# wireless_charger_controller.net
KiCad netlist of a schematic drawn in EasyEDA Pro
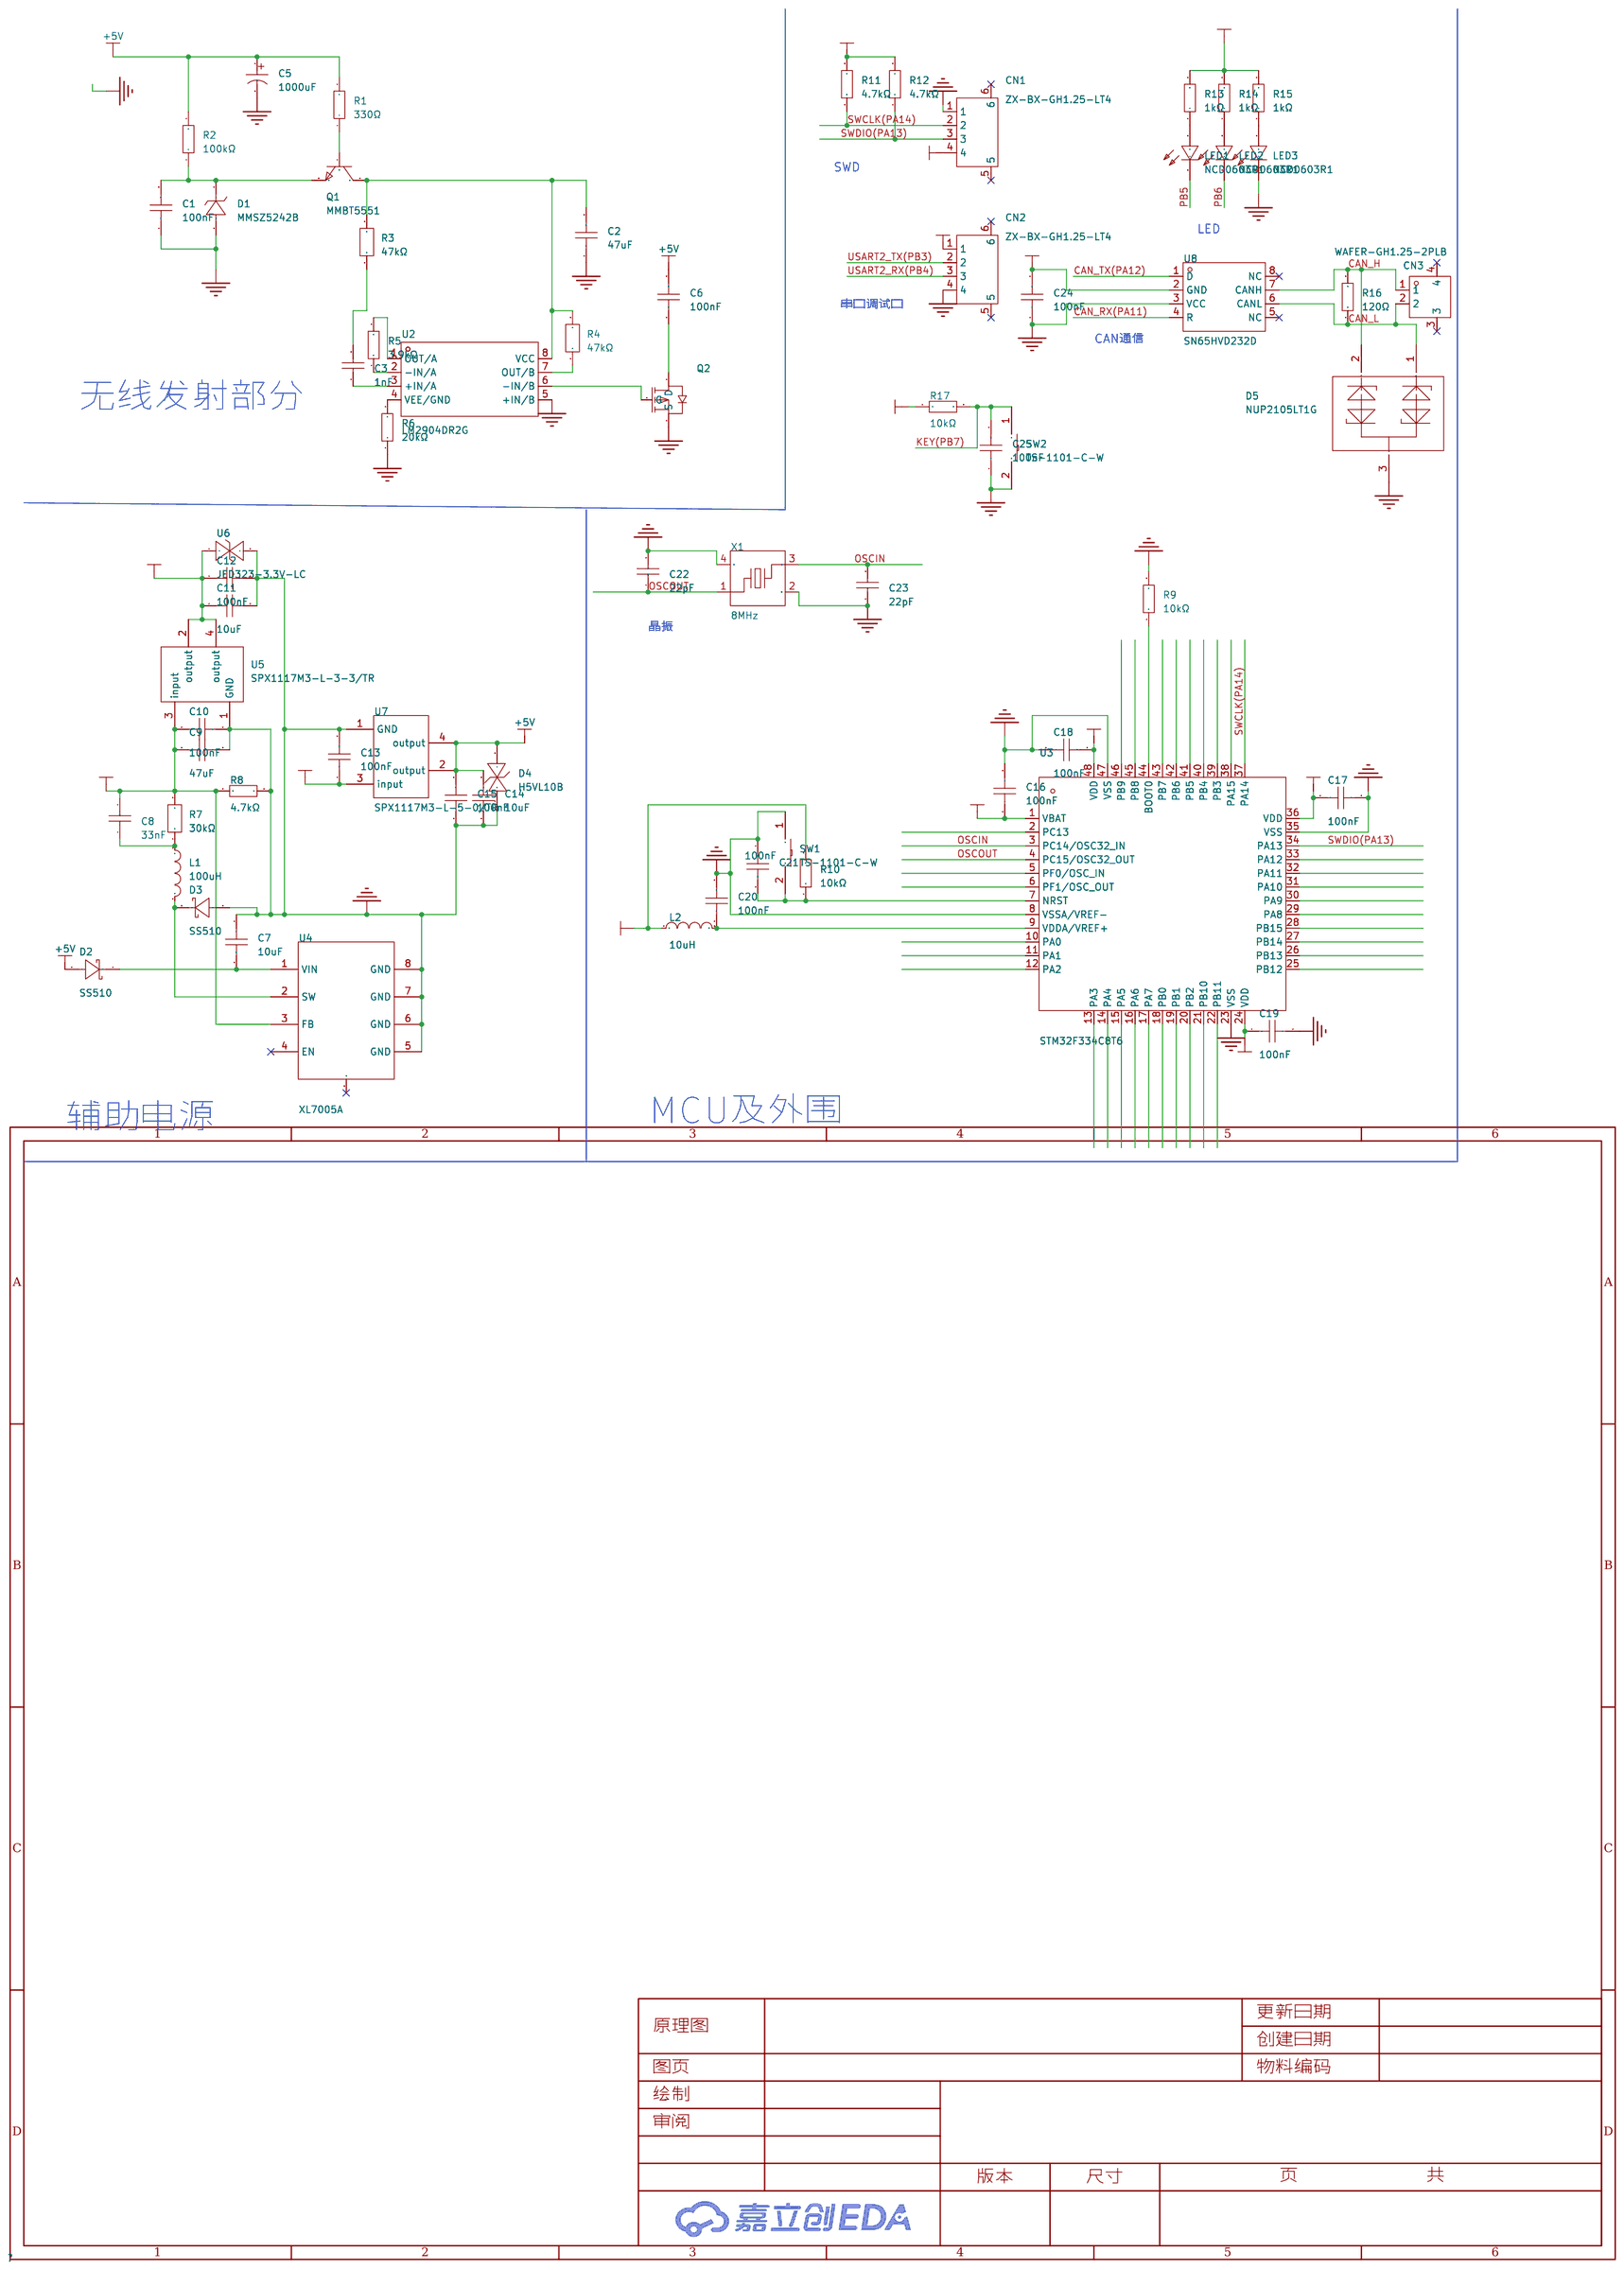
[diagram p0: schematic sheet]

(export (version "E")
  (design (tool "Eeschema 10.0.6"))
  (components
    (comp (ref "C1")
      (value "100nF")
      (footprint "easyedapro:C0603")
      (description "容值:100nF;精度:±10%;额定电压:50V;材质(温度系数):X7R;")
      (fields
        (field (name "Manufacturer Part") "CGA0603X7R104K500JT")
        (field (name "Manufacturer") "HRE(芯声)")
      )
      (libsource (lib "easyedapro") (part "CGA0603X7R104K500JT"))
    )
    (comp (ref "C2")
      (value "47uF")
      (footprint "easyedapro:C1206")
      (description "容值:47uF;精度:±20%;额定电压:16V;材质(温度系数):X5R;")
      (fields
        (field (name "Manufacturer Part") "HGC1206R5476M160NSPJ")
        (field (name "Manufacturer") "Chinocera(华瓷)")
      )
      (libsource (lib "easyedapro") (part "HGC1206R5476M160NSPJ"))
    )
    (comp (ref "C3")
      (value "1nF")
      (footprint "easyedapro:C0603")
      (description "容值:1nF;精度:±5%;额定电压:50V;材质(温度系数):NP0;")
      (fields
        (field (name "Manufacturer Part") "CC0603JRNPO9BN102")
        (field (name "Manufacturer") "YAGEO(国巨)")
      )
      (libsource (lib "easyedapro") (part "CC0603JRNPO9BN102"))
    )
    (comp (ref "C5")
      (value "1000uF")
      (footprint "easyedapro:CAP-TH_BD13.0-P5.00-D1.2-FD")
      (description "容值:1000uF;精度:±20%;额定电压:35V;")
      (fields
        (field (name "Manufacturer Part") "35YXJ1000M12.5X20")
        (field (name "Manufacturer") "rubycon(红宝石)")
      )
      (libsource (lib "easyedapro") (part "35YXJ1000M12.5X20"))
    )
    (comp (ref "C6")
      (value "100nF")
      (footprint "easyedapro:C1206")
      (description "容值:100nF;精度:±10%;额定电压:250V;材质(温度系数):X7R;")
      (fields
        (field (name "Manufacturer Part") "CGA1206X7R104K251NT")
        (field (name "Manufacturer") "HRE(芯声)")
      )
      (libsource (lib "easyedapro") (part "CGA1206X7R104K251NT"))
    )
    (comp (ref "C7")
      (value "10uF")
      (footprint "easyedapro:C1206")
      (description "容值:10uF;精度:±10%;额定电压:50V;材质(温度系数):X5R;")
      (fields
        (field (name "Manufacturer Part") "HGC1206R5106K500NSPJ")
        (field (name "Manufacturer") "Chinocera(华瓷)")
      )
      (libsource (lib "easyedapro") (part "HGC1206R5106K500NSPJ"))
    )
    (comp (ref "C8")
      (value "33nF")
      (footprint "easyedapro:C0603")
      (description "容值:33nF;精度:±10%;额定电压:50V;材质(温度系数):X7R;")
      (fields
        (field (name "Manufacturer Part") "CL10B333KB8NNNC")
        (field (name "Manufacturer") "SAMSUNG(三星)")
      )
      (libsource (lib "easyedapro") (part "CL10B333KB8NNNC"))
    )
    (comp (ref "C9")
      (value "47uF")
      (footprint "easyedapro:C1206")
      (description "容值:47uF;精度:±20%;额定电压:25V;材质(温度系数):X5R;")
      (fields
        (field (name "Manufacturer Part") "HGC1206R5476M250NSPJ")
        (field (name "Manufacturer") "Chinocera(华瓷)")
      )
      (libsource (lib "easyedapro") (part "HGC1206R5476M250NSPJ"))
    )
    (comp (ref "C10")
      (value "100nF")
      (footprint "easyedapro:C0603")
      (description "容值:100nF;精度:±10%;额定电压:50V;材质(温度系数):X7R;")
      (fields
        (field (name "Manufacturer Part") "CGA0603X7R104K500JT")
        (field (name "Manufacturer") "HRE(芯声)")
      )
      (libsource (lib "easyedapro") (part "CGA0603X7R104K500JT"))
    )
    (comp (ref "C11")
      (value "10uF")
      (footprint "easyedapro:C0603")
      (description "容值:10uF;精度:±10%;额定电压:10V;材质(温度系数):X5R;")
      (fields
        (field (name "Manufacturer Part") "CGA0603X5R106K100JT")
        (field (name "Manufacturer") "HRE(芯声)")
      )
      (libsource (lib "easyedapro") (part "CGA0603X5R106K100JT"))
    )
    (comp (ref "C12")
      (value "100nF")
      (footprint "easyedapro:C0603")
      (description "容值:100nF;精度:±10%;额定电压:50V;材质(温度系数):X7R;")
      (fields
        (field (name "Manufacturer Part") "CGA0603X7R104K500JT")
        (field (name "Manufacturer") "HRE(芯声)")
      )
      (libsource (lib "easyedapro") (part "CGA0603X7R104K500JT"))
    )
    (comp (ref "C13")
      (value "100nF")
      (footprint "easyedapro:C0603")
      (description "容值:100nF;精度:±10%;额定电压:50V;材质(温度系数):X7R;")
      (fields
        (field (name "Manufacturer Part") "CGA0603X7R104K500JT")
        (field (name "Manufacturer") "HRE(芯声)")
      )
      (libsource (lib "easyedapro") (part "CGA0603X7R104K500JT"))
    )
    (comp (ref "C14")
      (value "10uF")
      (footprint "easyedapro:C0603")
      (description "容值:10uF;精度:±10%;额定电压:10V;材质(温度系数):X5R;")
      (fields
        (field (name "Manufacturer Part") "CGA0603X5R106K100JT")
        (field (name "Manufacturer") "HRE(芯声)")
      )
      (libsource (lib "easyedapro") (part "CGA0603X5R106K100JT"))
    )
    (comp (ref "C15")
      (value "100nF")
      (footprint "easyedapro:C0603")
      (description "容值:100nF;精度:±10%;额定电压:50V;材质(温度系数):X7R;")
      (fields
        (field (name "Manufacturer Part") "CGA0603X7R104K500JT")
        (field (name "Manufacturer") "HRE(芯声)")
      )
      (libsource (lib "easyedapro") (part "CGA0603X7R104K500JT"))
    )
    (comp (ref "C16")
      (value "100nF")
      (footprint "easyedapro:C0603")
      (description "容值:100nF;精度:±10%;额定电压:50V;材质(温度系数):X7R;")
      (fields
        (field (name "Manufacturer Part") "CGA0603X7R104K500JT")
        (field (name "Manufacturer") "HRE(芯声)")
      )
      (libsource (lib "easyedapro") (part "CGA0603X7R104K500JT"))
    )
    (comp (ref "C17")
      (value "100nF")
      (footprint "easyedapro:C0603")
      (description "容值:100nF;精度:±10%;额定电压:50V;材质(温度系数):X7R;")
      (fields
        (field (name "Manufacturer Part") "CGA0603X7R104K500JT")
        (field (name "Manufacturer") "HRE(芯声)")
      )
      (libsource (lib "easyedapro") (part "CGA0603X7R104K500JT"))
    )
    (comp (ref "C18")
      (value "100nF")
      (footprint "easyedapro:C0603")
      (description "容值:100nF;精度:±10%;额定电压:50V;材质(温度系数):X7R;")
      (fields
        (field (name "Manufacturer Part") "CGA0603X7R104K500JT")
        (field (name "Manufacturer") "HRE(芯声)")
      )
      (libsource (lib "easyedapro") (part "CGA0603X7R104K500JT"))
    )
    (comp (ref "C19")
      (value "100nF")
      (footprint "easyedapro:C0603")
      (description "容值:100nF;精度:±10%;额定电压:50V;材质(温度系数):X7R;")
      (fields
        (field (name "Manufacturer Part") "CGA0603X7R104K500JT")
        (field (name "Manufacturer") "HRE(芯声)")
      )
      (libsource (lib "easyedapro") (part "CGA0603X7R104K500JT"))
    )
    (comp (ref "C20")
      (value "100nF")
      (footprint "easyedapro:C0603")
      (description "容值:100nF;精度:±10%;额定电压:50V;材质(温度系数):X7R;")
      (fields
        (field (name "Manufacturer Part") "CGA0603X7R104K500JT")
        (field (name "Manufacturer") "HRE(芯声)")
      )
      (libsource (lib "easyedapro") (part "CGA0603X7R104K500JT"))
    )
    (comp (ref "C21")
      (value "100nF")
      (footprint "easyedapro:C0603")
      (description "容值:100nF;精度:±10%;额定电压:50V;材质(温度系数):X7R;")
      (fields
        (field (name "Manufacturer Part") "CGA0603X7R104K500JT")
        (field (name "Manufacturer") "HRE(芯声)")
      )
      (libsource (lib "easyedapro") (part "CGA0603X7R104K500JT"))
    )
    (comp (ref "C22")
      (value "22pF")
      (footprint "easyedapro:C0603")
      (description "容值:22pF;精度:±5%;额定电压:50V;材质(温度系数):NP0;")
      (fields
        (field (name "Manufacturer Part") "CC0603JRNPO9BN220")
        (field (name "Manufacturer") "YAGEO(国巨)")
      )
      (libsource (lib "easyedapro") (part "CC0603JRNPO9BN220"))
    )
    (comp (ref "C23")
      (value "22pF")
      (footprint "easyedapro:C0603")
      (description "容值:22pF;精度:±5%;额定电压:50V;材质(温度系数):NP0;")
      (fields
        (field (name "Manufacturer Part") "CC0603JRNPO9BN220")
        (field (name "Manufacturer") "YAGEO(国巨)")
      )
      (libsource (lib "easyedapro") (part "CC0603JRNPO9BN220"))
    )
    (comp (ref "C24")
      (value "100nF")
      (footprint "easyedapro:C0603")
      (description "容值:100nF;精度:±10%;额定电压:50V;材质(温度系数):X7R;")
      (fields
        (field (name "Manufacturer Part") "CGA0603X7R104K500JT")
        (field (name "Manufacturer") "HRE(芯声)")
      )
      (libsource (lib "easyedapro") (part "CGA0603X7R104K500JT"))
    )
    (comp (ref "C25")
      (value "100nF")
      (footprint "easyedapro:C0603")
      (description "容值:100nF;精度:±10%;额定电压:50V;材质(温度系数):X7R;")
      (fields
        (field (name "Manufacturer Part") "CGA0603X7R104K500JT")
        (field (name "Manufacturer") "HRE(芯声)")
      )
      (libsource (lib "easyedapro") (part "CGA0603X7R104K500JT"))
    )
    (comp (ref "CN1")
      (value "ZX-BX-GH1.25-LT4")
      (footprint "easyedapro:CONN-SMD_ZX-BX-GH1.25-LT4")
      (description "插针结构:1x4P;间距:1.25mm;安装方式:立贴;参考系列:GH;总PIN数:4P;排数:1;每排PIN数:4;行距:-;额定电流:-;触头材质:磷铜;触头镀层:锡;工作温度:-;")
      (fields (field (name "Manufacturer") "Megastar(兆星)"))
      (libsource (lib "easyedapro") (part "ZX-BX-GH1.25-LT4"))
    )
    (comp (ref "CN2")
      (value "ZX-BX-GH1.25-LT4")
      (footprint "easyedapro:CONN-SMD_ZX-BX-GH1.25-LT4")
      (description "插针结构:1x4P;间距:1.25mm;安装方式:立贴;参考系列:GH;总PIN数:4P;排数:1;每排PIN数:4;行距:-;额定电流:-;触头材质:磷铜;触头镀层:锡;工作温度:-;")
      (fields (field (name "Manufacturer") "Megastar(兆星)"))
      (libsource (lib "easyedapro") (part "ZX-BX-GH1.25-LT4"))
    )
    (comp (ref "CN3")
      (value "WAFER-GH1.25-2PLB")
      (footprint "easyedapro:CONN-TH_2P-P1.25_XUNPU_WAFER-GH1.25-2PLB")
      (fields (field (name "Manufacturer") "XUNPU(讯普)"))
      (libsource (lib "easyedapro") (part "WAFER-GH1.25-2PLB"))
    )
    (comp (ref "D1")
      (value "MMSZ5242B")
      (footprint "easyedapro:SOD-123_L2.7-W1.6-LS3.7-RD")
      (description "二极管配置:独立式;稳压值(标称值):12V;稳压值(范围):11.4V~12.6V;耗散功率(Pd):500mW;")
      (fields (field (name "Manufacturer") "宏嘉诚"))
      (libsource (lib "easyedapro") (part "MMSZ5242B_C19077426"))
    )
    (comp (ref "D2")
      (value "SS510")
      (footprint "easyedapro:SMA_L4.3-W2.6-LS5.0-RD")
      (description "二极管配置:独立式;正向压降(Vf):850mV@5A;直流反向耐压(Vr):100V;整流电流:5A;")
      (fields (field (name "Manufacturer") "宏迦橙"))
      (libsource (lib "easyedapro") (part "SS510_C18199171"))
    )
    (comp (ref "D3")
      (value "SS510")
      (footprint "easyedapro:SMA_L4.3-W2.6-LS5.0-RD")
      (description "二极管配置:独立式;正向压降(Vf):850mV@5A;直流反向耐压(Vr):100V;整流电流:5A;")
      (fields (field (name "Manufacturer") "宏迦橙"))
      (libsource (lib "easyedapro") (part "SS510_C18199171"))
    )
    (comp (ref "D4")
      (value "H5VL10B")
      (footprint "easyedapro:SOD-882_L1.0-W0.6-BI")
      (description "极性:双向;反向截止电压(Vrwm):5V;最大钳位电压:10V;峰值脉冲电流(Ipp):5A;峰值脉冲功率(Ppp):50W;击穿电压:5.6V;")
      (fields (field (name "Manufacturer") "宏迦橙"))
      (libsource (lib "easyedapro") (part "H5VL10B"))
    )
    (comp (ref "D5")
      (value "NUP2105LT1G")
      (footprint "easyedapro:SOT-23-3_L2.9-W1.3-P1.90-LS2.4-BL-2")
      (description "反向截止电压(Vrwm):24V;最大钳位电压:44V;峰值脉冲功率(Ppp)@10/1000us:350W;击穿电压:26.2V;")
      (fields (field (name "Manufacturer") "onsemi(安森美)"))
      (libsource (lib "easyedapro") (part "NUP2105LT1G"))
    )
    (comp (ref "L1")
      (value "100uH")
      (footprint "easyedapro:IND-SMD_L6.0-W6.0_FNR60XXS")
      (description "电感值:100uH;精度:±20%;额定电流:880mA;饱和电流(Isat):1A;")
      (fields (field (name "Manufacturer Part") "FNR6045S101MT") (field (name "Manufacturer") "cjiang(长江微电)"))
      (libsource (lib "easyedapro") (part "FNR6045S101MT"))
    )
    (comp (ref "L2")
      (value "10uH")
      (footprint "easyedapro:L0603")
      (description "电感值:10uH;精度:±20%;额定电流:50mA;饱和电流(Isat):-;直流电阻(DCR):1.17Ω;")
      (fields (field (name "Manufacturer Part") "MCL1608S100MT") (field (name "Manufacturer") "Sunlord(顺络)"))
      (libsource (lib "easyedapro") (part "MCL1608S100MT"))
    )
    (comp (ref "LED1")
      (value "NCD0603R1")
      (footprint "easyedapro:LED0603-RD_RED")
      (fields (field (name "Manufacturer") "国星光电"))
      (libsource (lib "easyedapro") (part "FC-DA1608HRK-620D"))
    )
    (comp (ref "LED2")
      (value "NCD0603R1")
      (footprint "easyedapro:LED0603-RD_RED")
      (fields (field (name "Manufacturer") "国星光电"))
      (libsource (lib "easyedapro") (part "FC-DA1608HRK-620D"))
    )
    (comp (ref "LED3")
      (value "NCD0603R1")
      (footprint "easyedapro:LED0603-RD_RED")
      (fields (field (name "Manufacturer") "国星光电"))
      (libsource (lib "easyedapro") (part "FC-DA1608HRK-620D"))
    )
    (comp (ref "Q1")
      (value "MMBT5551")
      (footprint "easyedapro:SOT-23-3_L2.9-W1.3-P1.90-LS2.4-BR")
      (description "晶体管类型:NPN;集电极电流(Ic):600mA;集射极击穿电压(Vceo):160V;功率(Pd):300mW;直流电流增益(hFE@Ic,Vce):100@10mA,5.0V;")
      (fields (field (name "Manufacturer") "宏迦橙"))
      (libsource (lib "easyedapro") (part "MMBT5551_C7420357"))
    )
    (comp (ref "Q2")
      (value "~")
      (footprint "easyedapro:IRF9540P_TO-220")
      (libsource (lib "easyedapro") (part "IRF9540NPBF_P"))
    )
    (comp (ref "R1")
      (value "330Ω")
      (footprint "easyedapro:R0603")
      (description "电阻类型:厚膜电阻;阻值:330Ω;精度:±1%;功率:100mW;最大工作电压:75V;温度系数:±100ppm/°C;")
      (fields
        (field (name "Manufacturer Part") "0603WAF3300T5E")
        (field (name "Manufacturer") "UNI-ROYAL(厚声)")
      )
      (libsource (lib "easyedapro") (part "0603WAF3300T5E"))
    )
    (comp (ref "R2")
      (value "100kΩ")
      (footprint "easyedapro:R0603")
      (description "电阻类型:厚膜电阻;阻值:100kΩ;精度:±1%;功率:100mW;最大工作电压:75V;温度系数:±100ppm/°C;")
      (fields
        (field (name "Manufacturer Part") "0603WAF1003T5E")
        (field (name "Manufacturer") "UNI-ROYAL(厚声)")
      )
      (libsource (lib "easyedapro") (part "0603WAF1003T5E"))
    )
    (comp (ref "R3")
      (value "47kΩ")
      (footprint "easyedapro:R0603")
      (description "电阻类型:厚膜电阻;阻值:47kΩ;精度:±1%;功率:100mW;最大工作电压:75V;温度系数:±100ppm/°C;")
      (fields (field (name "Manufacturer Part") "FRC0603F4702TS") (field (name "Manufacturer") "FOJAN(富捷)"))
      (libsource (lib "easyedapro") (part "FRC0603F4702TS"))
    )
    (comp (ref "R4")
      (value "47kΩ")
      (footprint "easyedapro:R0603")
      (description "电阻类型:厚膜电阻;阻值:47kΩ;精度:±1%;功率:100mW;最大工作电压:75V;温度系数:±100ppm/°C;")
      (fields (field (name "Manufacturer Part") "FRC0603F4702TS") (field (name "Manufacturer") "FOJAN(富捷)"))
      (libsource (lib "easyedapro") (part "FRC0603F4702TS"))
    )
    (comp (ref "R5")
      (value "3.9kΩ")
      (footprint "easyedapro:R0603")
      (description "电阻类型:厚膜电阻;阻值:3.9kΩ;精度:±1%;功率:100mW;最大工作电压:75V;温度系数:±100ppm/°C;")
      (fields
        (field (name "Manufacturer Part") "0603WAF3901T5E")
        (field (name "Manufacturer") "UNI-ROYAL(厚声)")
      )
      (libsource (lib "easyedapro") (part "0603WAF3901T5E"))
    )
    (comp (ref "R6")
      (value "20kΩ")
      (footprint "easyedapro:R0603")
      (description "电阻类型:厚膜电阻;阻值:20kΩ;精度:±1%;功率:100mW;最大工作电压:75V;温度系数:±100ppm/°C;")
      (fields
        (field (name "Manufacturer Part") "0603WAF2002T5E")
        (field (name "Manufacturer") "UNI-ROYAL(厚声)")
      )
      (libsource (lib "easyedapro") (part "0603WAF2002T5E"))
    )
    (comp (ref "R7")
      (value "30kΩ")
      (footprint "easyedapro:R0603")
      (description "电阻类型:厚膜电阻;阻值:30kΩ;精度:±1%;功率:100mW;最大工作电压:75V;温度系数:±100ppm/°C;")
      (fields (field (name "Manufacturer Part") "FRC0603F3002TS") (field (name "Manufacturer") "FOJAN(富捷)"))
      (libsource (lib "easyedapro") (part "FRC0603F3002TS"))
    )
    (comp (ref "R8")
      (value "4.7kΩ")
      (footprint "easyedapro:R0603")
      (description "电阻类型:厚膜电阻;阻值:4.7kΩ;精度:±1%;功率:100mW;最大工作电压:75V;温度系数:±100ppm/°C;")
      (fields
        (field (name "Manufacturer Part") "0603WAF4701T5E")
        (field (name "Manufacturer") "UNI-ROYAL(厚声)")
      )
      (libsource (lib "easyedapro") (part "0603WAF4701T5E"))
    )
    (comp (ref "R9")
      (value "10kΩ")
      (footprint "easyedapro:R0603")
      (description "电阻类型:厚膜电阻;阻值:10kΩ;精度:±1%;功率:100mW;最大工作电压:75V;温度系数:±100ppm/°C;")
      (fields
        (field (name "Manufacturer Part") "0603WAF1002T5E")
        (field (name "Manufacturer") "UNI-ROYAL(厚声)")
      )
      (libsource (lib "easyedapro") (part "0603WAF1002T5E"))
    )
    (comp (ref "R10")
      (value "10kΩ")
      (footprint "easyedapro:R0603")
      (description "电阻类型:厚膜电阻;阻值:10kΩ;精度:±1%;功率:100mW;最大工作电压:75V;温度系数:±100ppm/°C;")
      (fields
        (field (name "Manufacturer Part") "0603WAF1002T5E")
        (field (name "Manufacturer") "UNI-ROYAL(厚声)")
      )
      (libsource (lib "easyedapro") (part "0603WAF1002T5E"))
    )
    (comp (ref "R11")
      (value "4.7kΩ")
      (footprint "easyedapro:R0603")
      (description "电阻类型:厚膜电阻;阻值:4.7kΩ;精度:±1%;功率:100mW;最大工作电压:75V;温度系数:±100ppm/°C;")
      (fields
        (field (name "Manufacturer Part") "0603WAF4701T5E")
        (field (name "Manufacturer") "UNI-ROYAL(厚声)")
      )
      (libsource (lib "easyedapro") (part "0603WAF4701T5E"))
    )
    (comp (ref "R12")
      (value "4.7kΩ")
      (footprint "easyedapro:R0603")
      (description "电阻类型:厚膜电阻;阻值:4.7kΩ;精度:±1%;功率:100mW;最大工作电压:75V;温度系数:±100ppm/°C;")
      (fields
        (field (name "Manufacturer Part") "0603WAF4701T5E")
        (field (name "Manufacturer") "UNI-ROYAL(厚声)")
      )
      (libsource (lib "easyedapro") (part "0603WAF4701T5E"))
    )
    (comp (ref "R13")
      (value "1kΩ")
      (footprint "easyedapro:R0603")
      (description "电阻类型:厚膜电阻;阻值:1kΩ;精度:±1%;功率:100mW;最大工作电压:75V;温度系数:±100ppm/°C;")
      (fields
        (field (name "Manufacturer Part") "0603WAF1001T5E")
        (field (name "Manufacturer") "UNI-ROYAL(厚声)")
      )
      (libsource (lib "easyedapro") (part "0603WAF1001T5E"))
    )
    (comp (ref "R14")
      (value "1kΩ")
      (footprint "easyedapro:R0603")
      (description "电阻类型:厚膜电阻;阻值:1kΩ;精度:±1%;功率:100mW;最大工作电压:75V;温度系数:±100ppm/°C;")
      (fields
        (field (name "Manufacturer Part") "0603WAF1001T5E")
        (field (name "Manufacturer") "UNI-ROYAL(厚声)")
      )
      (libsource (lib "easyedapro") (part "0603WAF1001T5E"))
    )
    (comp (ref "R15")
      (value "1kΩ")
      (footprint "easyedapro:R0603")
      (description "电阻类型:厚膜电阻;阻值:1kΩ;精度:±1%;功率:100mW;最大工作电压:75V;温度系数:±100ppm/°C;")
      (fields
        (field (name "Manufacturer Part") "0603WAF1001T5E")
        (field (name "Manufacturer") "UNI-ROYAL(厚声)")
      )
      (libsource (lib "easyedapro") (part "0603WAF1001T5E"))
    )
    (comp (ref "R16")
      (value "120Ω")
      (footprint "easyedapro:R0603")
      (description "电阻类型:厚膜电阻;阻值:120Ω;精度:±1%;功率:100mW;最大工作电压:75V;温度系数:±100ppm/°C;")
      (fields
        (field (name "Manufacturer Part") "0603WAF1200T5E")
        (field (name "Manufacturer") "UNI-ROYAL(厚声)")
      )
      (libsource (lib "easyedapro") (part "0603WAF1200T5E"))
    )
    (comp (ref "R17")
      (value "10kΩ")
      (footprint "easyedapro:R0603")
      (description "电阻类型:厚膜电阻;阻值:10kΩ;精度:±1%;功率:100mW;最大工作电压:75V;温度系数:±100ppm/°C;")
      (fields
        (field (name "Manufacturer Part") "0603WAF1002T5E")
        (field (name "Manufacturer") "UNI-ROYAL(厚声)")
      )
      (libsource (lib "easyedapro") (part "0603WAF1002T5E"))
    )
    (comp (ref "SW1")
      (value "TS-1101-C-W")
      (footprint "easyedapro:SW-SMD_L6.0-W3.3-LS8.0")
      (fields (field (name "Manufacturer") "XKB Connectivity(中国星坤)"))
      (libsource (lib "easyedapro") (part "TS-1101-C-W"))
    )
    (comp (ref "SW2")
      (value "TS-1101-C-W")
      (footprint "easyedapro:SW-SMD_L6.0-W3.3-LS8.0")
      (fields (field (name "Manufacturer") "XKB Connectivity(中国星坤)"))
      (libsource (lib "easyedapro") (part "TS-1101-C-W"))
    )
    (comp (ref "U2")
      (value "LM2904DR2G")
      (footprint "easyedapro:SOIC-8_L4.9-W3.9-P1.27-LS6.0-BL")
      (description "放大器数:双路;轨到轨:-;增益带宽积(GBP):1MHz;输入失调电压(Vos):7mV;压摆率(SR):-;输入偏置电流(Ib):45nA;")
      (fields (field (name "Manufacturer") "onsemi(安森美)"))
      (libsource (lib "easyedapro") (part "LM2904DR2G"))
    )
    (comp (ref "U3")
      (value "STM32F334C8T6")
      (footprint "easyedapro:LQFP-48_L7.0-W7.0-P0.50-LS9.0-BL")
      (description "CPU内核:ARM-M4;CPU最大主频:72MHz;应用领域:-;")
      (fields (field (name "Manufacturer") "ST(意法半导体)"))
      (libsource (lib "easyedapro") (part "STM32F334C8T6"))
    )
    (comp (ref "U4")
      (value "XL7005A")
      (footprint "easyedapro:SOIC-8_L4.9-W3.9-P1.27-LS6.0-BL-EP3.1-1")
      (description "功能类型:降压型;输出类型:可调;工作电压:5V~80V;输出电压:1.25V~20V;输出电流:400mA;")
      (fields (field (name "Manufacturer") "XLSEMI(芯龙)"))
      (libsource (lib "easyedapro") (part "XL7005A"))
    )
    (comp (ref "U5")
      (value "SPX1117M3-L-3-3/TR")
      (footprint "easyedapro:SOT-223-4_L6.5-W3.5-P2.30-LS7.0-BR")
      (description "输出类型:固定;最大输入电压:20V;输出电压:3.3V;最大输出电流:800mA;电源纹波抑制比(PSRR):70dB@(120Hz);输出极性:正极;")
      (fields (field (name "Manufacturer") "MaxLinear(迈凌)"))
      (libsource (lib "easyedapro") (part "SPX1117M3-L-3-3/TR"))
    )
    (comp (ref "U6")
      (value "JED323-3.3V-LC")
      (footprint "easyedapro:SOD-323_L1.7-W1.3-LS2.5-BI")
      (description "极性:双向;反向截止电压(Vrwm):3.3V;最大钳位电压:16V;峰值脉冲电流(Ipp):21A;峰值脉冲功率(Ppp):340W;击穿电压:3.3V;")
      (fields (field (name "Manufacturer") "JDTfuse(集电通)"))
      (libsource (lib "easyedapro") (part "JED323-3.3V-LC"))
    )
    (comp (ref "U7")
      (value "SPX1117M3-L-5-0/TR")
      (footprint "easyedapro:SOT-223-4_L6.5-W3.5-P2.30-LS7.0-BR")
      (description "输出类型:固定;最大输入电压:20V;输出电压:5V;输出电流:800mA;电源纹波抑制比(PSRR):75dB@(120Hz);输出极性:正极;")
      (fields (field (name "Manufacturer") "MaxLinear(迈凌)"))
      (libsource (lib "easyedapro") (part "SPX1117M3-L-5-0/TR"))
    )
    (comp (ref "U8")
      (value "SN65HVD232D")
      (footprint "easyedapro:SOIC-8_L4.9-W3.9-P1.27-LS6.0-TL")
      (description "类型:CAN收发器;数据速率:1Mbps;")
      (fields (field (name "Manufacturer") "TI(德州仪器)"))
      (libsource (lib "easyedapro") (part "SN65HVD232D"))
    )
    (comp (ref "X1")
      (value "8MHz")
      (footprint "easyedapro:CRYSTAL-SMD_4P-L3.2-W2.5-BL")
      (description "晶振类型:贴片晶振;频率:8MHz;常温频差:±10ppm;负载电容:12pF;频率稳定度:±20ppm;")
      (fields (field (name "Manufacturer Part") "X32258MOB4SI") (field (name "Manufacturer") "YXC(扬兴晶振)"))
      (libsource (lib "easyedapro") (part "X32258MOB4SI"))
    )
  )
  (nets
    (net (code "1") (name "+3.3V") (class "Default")
      (node (ref "C11") (pin "1") (pinfunction "1_1") (pintype "unspecified"))
      (node (ref "C12") (pin "1") (pinfunction "1_1") (pintype "unspecified"))
      (node (ref "C16") (pin "1") (pinfunction "1_1") (pintype "unspecified"))
      (node (ref "C17") (pin "1") (pinfunction "1_1") (pintype "unspecified"))
      (node (ref "C18") (pin "2") (pinfunction "2_2") (pintype "unspecified"))
      (node (ref "C19") (pin "1") (pinfunction "1_1") (pintype "unspecified"))
      (node (ref "C24") (pin "2") (pinfunction "2_2") (pintype "unspecified"))
      (node (ref "CN1") (pin "4") (pinfunction "4_4") (pintype "unspecified"))
      (node (ref "CN2") (pin "1") (pinfunction "1_1") (pintype "unspecified"))
      (node (ref "L2") (pin "1") (pinfunction "1_1") (pintype "unspecified"))
      (node (ref "R10") (pin "1") (pinfunction "1_1") (pintype "input"))
      (node (ref "R11") (pin "2") (pinfunction "2_2") (pintype "input"))
      (node (ref "R12") (pin "2") (pinfunction "2_2") (pintype "input"))
      (node (ref "R13") (pin "2") (pinfunction "2_2") (pintype "input"))
      (node (ref "R14") (pin "2") (pinfunction "2_2") (pintype "input"))
      (node (ref "R15") (pin "2") (pinfunction "2_2") (pintype "input"))
      (node (ref "R17") (pin "1") (pinfunction "1_1") (pintype "input"))
      (node (ref "U3") (pin "1") (pinfunction "VBAT_1") (pintype "unspecified"))
      (node (ref "U3") (pin "24") (pinfunction "VDD_24") (pintype "unspecified"))
      (node (ref "U3") (pin "36") (pinfunction "VDD_36") (pintype "unspecified"))
      (node (ref "U3") (pin "48") (pinfunction "VDD_48") (pintype "unspecified"))
      (node (ref "U5") (pin "2") (pinfunction "output_2") (pintype "unspecified"))
      (node (ref "U5") (pin "4") (pinfunction "output_4") (pintype "unspecified"))
      (node (ref "U6") (pin "1") (pinfunction "K_1") (pintype "unspecified"))
      (node (ref "U8") (pin "2") (pinfunction "GND_2") (pintype "unspecified"))
    )
    (net (code "2") (name "+5V") (class "Default")
      (node (ref "C14") (pin "2") (pinfunction "2_2") (pintype "unspecified"))
      (node (ref "C15") (pin "2") (pinfunction "2_2") (pintype "unspecified"))
      (node (ref "C5") (pin "1") (pinfunction "1_1") (pintype "input"))
      (node (ref "C6") (pin "2") (pinfunction "2_2") (pintype "unspecified"))
      (node (ref "D2") (pin "2") (pinfunction "A_2") (pintype "unspecified"))
      (node (ref "D4") (pin "2") (pinfunction "A_2") (pintype "unspecified"))
      (node (ref "R1") (pin "2") (pinfunction "2_2") (pintype "input"))
      (node (ref "R2") (pin "2") (pinfunction "2_2") (pintype "input"))
      (node (ref "U7") (pin "2") (pinfunction "output_2") (pintype "unspecified"))
      (node (ref "U7") (pin "4") (pinfunction "output_4") (pintype "unspecified"))
    )
    (net (code "3") (name "+9.5V") (class "Default")
      (node (ref "C10") (pin "1") (pinfunction "1_1") (pintype "unspecified"))
      (node (ref "C13") (pin "1") (pinfunction "1_1") (pintype "unspecified"))
      (node (ref "C8") (pin "2") (pinfunction "2_2") (pintype "input"))
      (node (ref "C9") (pin "1") (pinfunction "1_1") (pintype "unspecified"))
      (node (ref "R7") (pin "2") (pinfunction "2_2") (pintype "unspecified"))
      (node (ref "R8") (pin "2") (pinfunction "2_2") (pintype "input"))
      (node (ref "U4") (pin "3") (pinfunction "FB_3") (pintype "unspecified"))
      (node (ref "U5") (pin "3") (pinfunction "input_3") (pintype "unspecified"))
      (node (ref "U7") (pin "3") (pinfunction "input_3") (pintype "unspecified"))
    )
    (net (code "4") (name "/CAN_H") (class "Default")
      (node (ref "CN3") (pin "1") (pinfunction "1_1") (pintype "unspecified"))
      (node (ref "D5") (pin "2") (pinfunction "2_2") (pintype "input"))
      (node (ref "R16") (pin "2") (pinfunction "2_2") (pintype "input"))
      (node (ref "U8") (pin "7") (pinfunction "CANH_7") (pintype "unspecified"))
    )
    (net (code "5") (name "/CAN_L") (class "Default")
      (node (ref "CN3") (pin "2") (pinfunction "2_2") (pintype "unspecified"))
      (node (ref "D5") (pin "1") (pinfunction "1_1") (pintype "input"))
      (node (ref "R16") (pin "1") (pinfunction "1_1") (pintype "input"))
      (node (ref "U8") (pin "6") (pinfunction "CANL_6") (pintype "unspecified"))
    )
    (net (code "6") (name "/CAN_RX(PA11)") (class "Default")
      (node (ref "U8") (pin "4") (pinfunction "R_4") (pintype "unspecified"))
    )
    (net (code "7") (name "/CAN_TX(PA12)") (class "Default")
      (node (ref "U8") (pin "1") (pinfunction "D_1") (pintype "unspecified"))
    )
    (net (code "8") (name "/KEY(PB7)") (class "Default")
      (node (ref "C25") (pin "2") (pinfunction "2_2") (pintype "unspecified"))
      (node (ref "R17") (pin "2") (pinfunction "2_2") (pintype "input"))
      (node (ref "SW2") (pin "1") (pinfunction "1_1") (pintype "unspecified"))
    )
    (net (code "9") (name "/OSCIN") (class "Default")
      (node (ref "C23") (pin "2") (pinfunction "2_2") (pintype "input"))
      (node (ref "U3") (pin "3") (pinfunction "PC14/OSC32_IN_3") (pintype "unspecified"))
      (node (ref "X1") (pin "3") (pinfunction "3_3") (pintype "input"))
    )
    (net (code "10") (name "/OSCOUT") (class "Default")
      (node (ref "C22") (pin "1") (pinfunction "1_1") (pintype "input"))
      (node (ref "U3") (pin "4") (pinfunction "PC15/OSC32_OUT_4") (pintype "unspecified"))
      (node (ref "X1") (pin "1") (pinfunction "1_1") (pintype "input"))
    )
    (net (code "11") (name "/PB5") (class "Default")
      (node (ref "LED1") (pin "1") (pinfunction "K_1") (pintype "input"))
    )
    (net (code "12") (name "/PB6") (class "Default")
      (node (ref "LED2") (pin "1") (pinfunction "K_1") (pintype "input"))
    )
    (net (code "13") (name "/SWCLK(PA14)") (class "Default")
      (node (ref "CN1") (pin "2") (pinfunction "2_2") (pintype "unspecified"))
      (node (ref "R11") (pin "1") (pinfunction "1_1") (pintype "input"))
      (node (ref "U3") (pin "37") (pinfunction "PA14_37") (pintype "unspecified"))
    )
    (net (code "14") (name "/SWDIO(PA13)") (class "Default")
      (node (ref "CN1") (pin "3") (pinfunction "3_3") (pintype "unspecified"))
      (node (ref "R12") (pin "1") (pinfunction "1_1") (pintype "input"))
      (node (ref "U3") (pin "34") (pinfunction "PA13_34") (pintype "unspecified"))
    )
    (net (code "15") (name "/USART2_RX(PB4)") (class "Default")
      (node (ref "CN2") (pin "3") (pinfunction "3_3") (pintype "unspecified"))
    )
    (net (code "16") (name "/USART2_TX(PB3)") (class "Default")
      (node (ref "CN2") (pin "2") (pinfunction "2_2") (pintype "unspecified"))
    )
    (net (code "17") (name "GND") (class "Default")
      (node (ref "C1") (pin "1") (pinfunction "1_1") (pintype "unspecified"))
      (node (ref "C10") (pin "2") (pinfunction "2_2") (pintype "unspecified"))
      (node (ref "C11") (pin "2") (pinfunction "2_2") (pintype "unspecified"))
      (node (ref "C12") (pin "2") (pinfunction "2_2") (pintype "unspecified"))
      (node (ref "C13") (pin "2") (pinfunction "2_2") (pintype "unspecified"))
      (node (ref "C14") (pin "1") (pinfunction "1_1") (pintype "unspecified"))
      (node (ref "C15") (pin "1") (pinfunction "1_1") (pintype "unspecified"))
      (node (ref "C16") (pin "2") (pinfunction "2_2") (pintype "unspecified"))
      (node (ref "C17") (pin "2") (pinfunction "2_2") (pintype "unspecified"))
      (node (ref "C18") (pin "1") (pinfunction "1_1") (pintype "unspecified"))
      (node (ref "C19") (pin "2") (pinfunction "2_2") (pintype "unspecified"))
      (node (ref "C2") (pin "1") (pinfunction "1_1") (pintype "unspecified"))
      (node (ref "C20") (pin "2") (pinfunction "2_2") (pintype "unspecified"))
      (node (ref "C21") (pin "1") (pinfunction "1_1") (pintype "unspecified"))
      (node (ref "C22") (pin "2") (pinfunction "2_2") (pintype "input"))
      (node (ref "C23") (pin "1") (pinfunction "1_1") (pintype "input"))
      (node (ref "C24") (pin "1") (pinfunction "1_1") (pintype "unspecified"))
      (node (ref "C25") (pin "1") (pinfunction "1_1") (pintype "unspecified"))
      (node (ref "C5") (pin "2") (pinfunction "2_2") (pintype "input"))
      (node (ref "C7") (pin "1") (pinfunction "1_1") (pintype "unspecified"))
      (node (ref "C9") (pin "2") (pinfunction "2_2") (pintype "unspecified"))
      (node (ref "CN1") (pin "1") (pinfunction "1_1") (pintype "unspecified"))
      (node (ref "CN2") (pin "4") (pinfunction "4_4") (pintype "unspecified"))
      (node (ref "D1") (pin "2") (pinfunction "A_2") (pintype "unspecified"))
      (node (ref "D3") (pin "2") (pinfunction "A_2") (pintype "unspecified"))
      (node (ref "D4") (pin "1") (pinfunction "C_1") (pintype "unspecified"))
      (node (ref "D5") (pin "3") (pinfunction "3_3") (pintype "input"))
      (node (ref "LED3") (pin "1") (pinfunction "K_1") (pintype "input"))
      (node (ref "Q2") (pin "3") (pinfunction "S_3") (pintype "input"))
      (node (ref "R6") (pin "1") (pinfunction "1_1") (pintype "input"))
      (node (ref "R8") (pin "1") (pinfunction "1_1") (pintype "input"))
      (node (ref "R9") (pin "2") (pinfunction "2_2") (pintype "input"))
      (node (ref "SW1") (pin "1") (pinfunction "1_1") (pintype "unspecified"))
      (node (ref "SW2") (pin "2") (pinfunction "2_2") (pintype "unspecified"))
      (node (ref "U2") (pin "5") (pinfunction "+IN/B_5") (pintype "unspecified"))
      (node (ref "U3") (pin "23") (pinfunction "VSS_23") (pintype "unspecified"))
      (node (ref "U3") (pin "35") (pinfunction "VSS_35") (pintype "unspecified"))
      (node (ref "U3") (pin "47") (pinfunction "VSS_47") (pintype "unspecified"))
      (node (ref "U3") (pin "8") (pinfunction "VSSA/VREF-_8") (pintype "unspecified"))
      (node (ref "U4") (pin "5") (pinfunction "GND_5") (pintype "unspecified"))
      (node (ref "U4") (pin "6") (pinfunction "GND_6") (pintype "unspecified"))
      (node (ref "U4") (pin "7") (pinfunction "GND_7") (pintype "unspecified"))
      (node (ref "U4") (pin "8") (pinfunction "GND_8") (pintype "unspecified"))
      (node (ref "U5") (pin "1") (pinfunction "GND_1") (pintype "unspecified"))
      (node (ref "U6") (pin "2") (pinfunction "A_2") (pintype "unspecified"))
      (node (ref "U7") (pin "1") (pinfunction "GND_1") (pintype "unspecified"))
      (node (ref "U8") (pin "3") (pinfunction "VCC_3") (pintype "unspecified"))
      (node (ref "X1") (pin "2") (pinfunction "GND_2") (pintype "input"))
      (node (ref "X1") (pin "4") (pinfunction "GND_4") (pintype "input"))
    )
    (net (code "18") (name "Net-(C3-Pad2)") (class "Default")
      (node (ref "C3") (pin "2") (pinfunction "2_2") (pintype "input"))
      (node (ref "R3") (pin "1") (pinfunction "1_1") (pintype "unspecified"))
    )
    (net (code "19") (name "Net-(C8-Pad1)") (class "Default")
      (node (ref "C8") (pin "1") (pinfunction "1_1") (pintype "input"))
      (node (ref "L1") (pin "1") (pinfunction "1_1") (pintype "unspecified"))
      (node (ref "R7") (pin "1") (pinfunction "1_1") (pintype "unspecified"))
    )
    (net (code "20") (name "Net-(D1-K)") (class "Default")
      (node (ref "C1") (pin "2") (pinfunction "2_2") (pintype "unspecified"))
      (node (ref "D1") (pin "1") (pinfunction "K_1") (pintype "unspecified"))
      (node (ref "Q1") (pin "2") (pinfunction "E_2") (pintype "input"))
      (node (ref "R2") (pin "1") (pinfunction "1_1") (pintype "input"))
    )
    (net (code "21") (name "Net-(D2-K)") (class "Default")
      (node (ref "C7") (pin "2") (pinfunction "2_2") (pintype "unspecified"))
      (node (ref "D2") (pin "1") (pinfunction "K_1") (pintype "unspecified"))
      (node (ref "U4") (pin "1") (pinfunction "VIN_1") (pintype "unspecified"))
    )
    (net (code "22") (name "Net-(D3-K)") (class "Default")
      (node (ref "D3") (pin "1") (pinfunction "K_1") (pintype "unspecified"))
      (node (ref "L1") (pin "2") (pinfunction "2_2") (pintype "unspecified"))
      (node (ref "U4") (pin "2") (pinfunction "SW_2") (pintype "unspecified"))
    )
    (net (code "23") (name "Net-(LED1-A)") (class "Default")
      (node (ref "LED1") (pin "2") (pinfunction "A_2") (pintype "input"))
      (node (ref "R13") (pin "1") (pinfunction "1_1") (pintype "input"))
    )
    (net (code "24") (name "Net-(LED2-A)") (class "Default")
      (node (ref "LED2") (pin "2") (pinfunction "A_2") (pintype "input"))
      (node (ref "R14") (pin "1") (pinfunction "1_1") (pintype "input"))
    )
    (net (code "25") (name "Net-(LED3-A)") (class "Default")
      (node (ref "LED3") (pin "2") (pinfunction "A_2") (pintype "input"))
      (node (ref "R15") (pin "1") (pinfunction "1_1") (pintype "input"))
    )
    (net (code "26") (name "Net-(Q1-B)") (class "Default")
      (node (ref "Q1") (pin "1") (pinfunction "B_1") (pintype "input"))
      (node (ref "R1") (pin "1") (pinfunction "1_1") (pintype "input"))
    )
    (net (code "27") (name "Net-(Q1-C)") (class "Default")
      (node (ref "C2") (pin "2") (pinfunction "2_2") (pintype "unspecified"))
      (node (ref "Q1") (pin "3") (pinfunction "C_3") (pintype "input"))
      (node (ref "R3") (pin "2") (pinfunction "2_2") (pintype "unspecified"))
      (node (ref "R4") (pin "2") (pinfunction "2_2") (pintype "unspecified"))
      (node (ref "U2") (pin "8") (pinfunction "VCC_8") (pintype "unspecified"))
    )
    (net (code "28") (name "Net-(Q2-D)") (class "Default")
      (node (ref "C6") (pin "1") (pinfunction "1_1") (pintype "unspecified"))
      (node (ref "Q2") (pin "2") (pinfunction "D_2") (pintype "input"))
    )
    (net (code "29") (name "Net-(Q2-G)") (class "Default")
      (node (ref "Q2") (pin "1") (pinfunction "G_1") (pintype "input"))
      (node (ref "U2") (pin "6") (pinfunction "-IN/B_6") (pintype "unspecified"))
    )
    (net (code "30") (name "Net-(U2-+IN{slash}A)") (class "Default")
      (node (ref "C3") (pin "1") (pinfunction "1_1") (pintype "input"))
      (node (ref "U2") (pin "3") (pinfunction "+IN/A_3") (pintype "unspecified"))
    )
    (net (code "31") (name "Net-(U2--IN{slash}A)") (class "Default")
      (node (ref "R5") (pin "1") (pinfunction "1_1") (pintype "input"))
      (node (ref "U2") (pin "2") (pinfunction "-IN/A_2") (pintype "unspecified"))
    )
    (net (code "32") (name "Net-(U2-OUT{slash}A)") (class "Default")
      (node (ref "R5") (pin "2") (pinfunction "2_2") (pintype "input"))
      (node (ref "U2") (pin "1") (pinfunction "OUT/A_1") (pintype "unspecified"))
    )
    (net (code "33") (name "Net-(U2-OUT{slash}B)") (class "Default")
      (node (ref "R4") (pin "1") (pinfunction "1_1") (pintype "unspecified"))
      (node (ref "U2") (pin "7") (pinfunction "OUT/B_7") (pintype "unspecified"))
    )
    (net (code "34") (name "Net-(U2-VEE{slash}GND)") (class "Default")
      (node (ref "R6") (pin "2") (pinfunction "2_2") (pintype "input"))
      (node (ref "U2") (pin "4") (pinfunction "VEE/GND_4") (pintype "unspecified"))
    )
    (net (code "35") (name "Net-(U3-BOOT0)") (class "Default")
      (node (ref "R9") (pin "1") (pinfunction "1_1") (pintype "input"))
      (node (ref "U3") (pin "44") (pinfunction "BOOT0_44") (pintype "unspecified"))
    )
    (net (code "36") (name "Net-(U3-NRST)") (class "Default")
      (node (ref "C21") (pin "2") (pinfunction "2_2") (pintype "unspecified"))
      (node (ref "R10") (pin "2") (pinfunction "2_2") (pintype "input"))
      (node (ref "SW1") (pin "2") (pinfunction "2_2") (pintype "unspecified"))
      (node (ref "U3") (pin "7") (pinfunction "NRST_7") (pintype "unspecified"))
    )
    (net (code "37") (name "Net-(U3-VDDA{slash}VREF+)") (class "Default")
      (node (ref "C20") (pin "1") (pinfunction "1_1") (pintype "unspecified"))
      (node (ref "L2") (pin "2") (pinfunction "2_2") (pintype "unspecified"))
      (node (ref "U3") (pin "9") (pinfunction "VDDA/VREF+_9") (pintype "unspecified"))
    )
    (net (code "38") (name "unconnected-(CN1-Pad5)") (class "Default")
      (node (ref "CN1") (pin "5") (pinfunction "5_5") (pintype "unspecified+no_connect"))
    )
    (net (code "39") (name "unconnected-(CN1-Pad6)") (class "Default")
      (node (ref "CN1") (pin "6") (pinfunction "6_6") (pintype "unspecified+no_connect"))
    )
    (net (code "40") (name "unconnected-(CN2-Pad5)") (class "Default")
      (node (ref "CN2") (pin "5") (pinfunction "5_5") (pintype "unspecified+no_connect"))
    )
    (net (code "41") (name "unconnected-(CN2-Pad6)") (class "Default")
      (node (ref "CN2") (pin "6") (pinfunction "6_6") (pintype "unspecified+no_connect"))
    )
    (net (code "42") (name "unconnected-(CN3-Pad3)") (class "Default")
      (node (ref "CN3") (pin "3") (pinfunction "3_3") (pintype "unspecified+no_connect"))
    )
    (net (code "43") (name "unconnected-(CN3-Pad4)") (class "Default")
      (node (ref "CN3") (pin "4") (pinfunction "4_4") (pintype "unspecified+no_connect"))
    )
    (net (code "44") (name "unconnected-(U3-PA0-Pad10)") (class "Default")
      (node (ref "U3") (pin "10") (pinfunction "PA0_10") (pintype "unspecified"))
    )
    (net (code "45") (name "unconnected-(U3-PA1-Pad11)") (class "Default")
      (node (ref "U3") (pin "11") (pinfunction "PA1_11") (pintype "unspecified"))
    )
    (net (code "46") (name "unconnected-(U3-PA2-Pad12)") (class "Default")
      (node (ref "U3") (pin "12") (pinfunction "PA2_12") (pintype "unspecified"))
    )
    (net (code "47") (name "unconnected-(U3-PA3-Pad13)") (class "Default")
      (node (ref "U3") (pin "13") (pinfunction "PA3_13") (pintype "unspecified"))
    )
    (net (code "48") (name "unconnected-(U3-PA4-Pad14)") (class "Default")
      (node (ref "U3") (pin "14") (pinfunction "PA4_14") (pintype "unspecified"))
    )
    (net (code "49") (name "unconnected-(U3-PA5-Pad15)") (class "Default")
      (node (ref "U3") (pin "15") (pinfunction "PA5_15") (pintype "unspecified"))
    )
    (net (code "50") (name "unconnected-(U3-PA6-Pad16)") (class "Default")
      (node (ref "U3") (pin "16") (pinfunction "PA6_16") (pintype "unspecified"))
    )
    (net (code "51") (name "unconnected-(U3-PA7-Pad17)") (class "Default")
      (node (ref "U3") (pin "17") (pinfunction "PA7_17") (pintype "unspecified"))
    )
    (net (code "52") (name "unconnected-(U3-PA8-Pad29)") (class "Default")
      (node (ref "U3") (pin "29") (pinfunction "PA8_29") (pintype "unspecified"))
    )
    (net (code "53") (name "unconnected-(U3-PA9-Pad30)") (class "Default")
      (node (ref "U3") (pin "30") (pinfunction "PA9_30") (pintype "unspecified"))
    )
    (net (code "54") (name "unconnected-(U3-PA10-Pad31)") (class "Default")
      (node (ref "U3") (pin "31") (pinfunction "PA10_31") (pintype "unspecified"))
    )
    (net (code "55") (name "unconnected-(U3-PA11-Pad32)") (class "Default")
      (node (ref "U3") (pin "32") (pinfunction "PA11_32") (pintype "unspecified"))
    )
    (net (code "56") (name "unconnected-(U3-PA12-Pad33)") (class "Default")
      (node (ref "U3") (pin "33") (pinfunction "PA12_33") (pintype "unspecified"))
    )
    (net (code "57") (name "unconnected-(U3-PA15-Pad38)") (class "Default")
      (node (ref "U3") (pin "38") (pinfunction "PA15_38") (pintype "unspecified"))
    )
    (net (code "58") (name "unconnected-(U3-PB0-Pad18)") (class "Default")
      (node (ref "U3") (pin "18") (pinfunction "PB0_18") (pintype "unspecified"))
    )
    (net (code "59") (name "unconnected-(U3-PB1-Pad19)") (class "Default")
      (node (ref "U3") (pin "19") (pinfunction "PB1_19") (pintype "unspecified"))
    )
    (net (code "60") (name "unconnected-(U3-PB2-Pad20)") (class "Default")
      (node (ref "U3") (pin "20") (pinfunction "PB2_20") (pintype "unspecified"))
    )
    (net (code "61") (name "unconnected-(U3-PB3-Pad39)") (class "Default")
      (node (ref "U3") (pin "39") (pinfunction "PB3_39") (pintype "unspecified"))
    )
    (net (code "62") (name "unconnected-(U3-PB4-Pad40)") (class "Default")
      (node (ref "U3") (pin "40") (pinfunction "PB4_40") (pintype "unspecified"))
    )
    (net (code "63") (name "unconnected-(U3-PB5-Pad41)") (class "Default")
      (node (ref "U3") (pin "41") (pinfunction "PB5_41") (pintype "unspecified"))
    )
    (net (code "64") (name "unconnected-(U3-PB6-Pad42)") (class "Default")
      (node (ref "U3") (pin "42") (pinfunction "PB6_42") (pintype "unspecified"))
    )
    (net (code "65") (name "unconnected-(U3-PB7-Pad43)") (class "Default")
      (node (ref "U3") (pin "43") (pinfunction "PB7_43") (pintype "unspecified"))
    )
    (net (code "66") (name "unconnected-(U3-PB8-Pad45)") (class "Default")
      (node (ref "U3") (pin "45") (pinfunction "PB8_45") (pintype "unspecified"))
    )
    (net (code "67") (name "unconnected-(U3-PB9-Pad46)") (class "Default")
      (node (ref "U3") (pin "46") (pinfunction "PB9_46") (pintype "unspecified"))
    )
    (net (code "68") (name "unconnected-(U3-PB10-Pad21)") (class "Default")
      (node (ref "U3") (pin "21") (pinfunction "PB10_21") (pintype "unspecified"))
    )
    (net (code "69") (name "unconnected-(U3-PB11-Pad22)") (class "Default")
      (node (ref "U3") (pin "22") (pinfunction "PB11_22") (pintype "unspecified"))
    )
    (net (code "70") (name "unconnected-(U3-PB12-Pad25)") (class "Default")
      (node (ref "U3") (pin "25") (pinfunction "PB12_25") (pintype "unspecified"))
    )
    (net (code "71") (name "unconnected-(U3-PB13-Pad26)") (class "Default")
      (node (ref "U3") (pin "26") (pinfunction "PB13_26") (pintype "unspecified"))
    )
    (net (code "72") (name "unconnected-(U3-PB14-Pad27)") (class "Default")
      (node (ref "U3") (pin "27") (pinfunction "PB14_27") (pintype "unspecified"))
    )
    (net (code "73") (name "unconnected-(U3-PB15-Pad28)") (class "Default")
      (node (ref "U3") (pin "28") (pinfunction "PB15_28") (pintype "unspecified"))
    )
    (net (code "74") (name "unconnected-(U3-PC13-Pad2)") (class "Default")
      (node (ref "U3") (pin "2") (pinfunction "PC13_2") (pintype "unspecified"))
    )
    (net (code "75") (name "unconnected-(U3-PF0{slash}OSC_IN-Pad5)") (class "Default")
      (node (ref "U3") (pin "5") (pinfunction "PF0/OSC_IN_5") (pintype "unspecified"))
    )
    (net (code "76") (name "unconnected-(U3-PF1{slash}OSC_OUT-Pad6)") (class "Default")
      (node (ref "U3") (pin "6") (pinfunction "PF1/OSC_OUT_6") (pintype "unspecified"))
    )
    (net (code "77") (name "unconnected-(U4-EN-Pad4)") (class "Default")
      (node (ref "U4") (pin "4") (pinfunction "EN_4") (pintype "unspecified+no_connect"))
    )
    (net (code "78") (name "unconnected-(U4-Pad9)") (class "Default")
      (node (ref "U4") (pin "9") (pinfunction "9_9") (pintype "unspecified+no_connect"))
    )
    (net (code "79") (name "unconnected-(U8-NC-Pad5)") (class "Default")
      (node (ref "U8") (pin "5") (pinfunction "NC_5") (pintype "unspecified+no_connect"))
    )
    (net (code "80") (name "unconnected-(U8-NC-Pad8)") (class "Default")
      (node (ref "U8") (pin "8") (pinfunction "NC_8") (pintype "unspecified+no_connect"))
    )
  )
)
